# ADC.net
KiCad netlist of a schematic drawn in Altium Designer
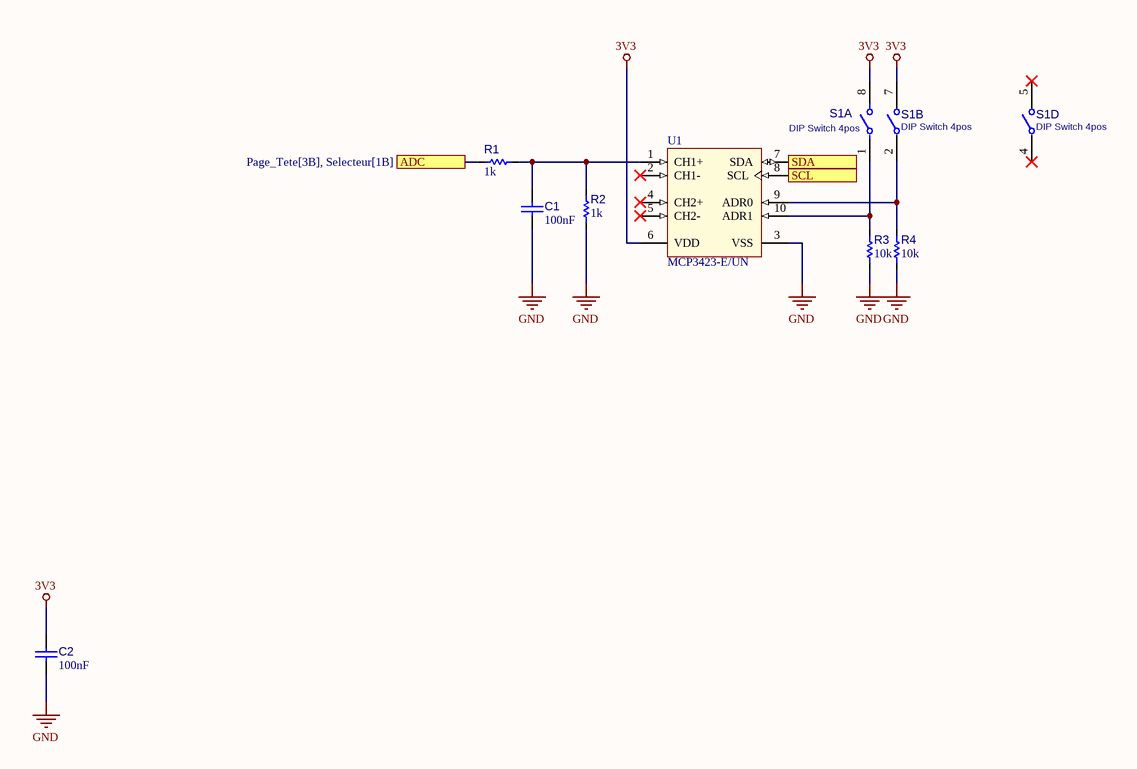
[diagram p0: ADC.SchDoc]

(export (version "E")
  (design (tool "Eeschema 10.0.6"))
  (components
    (comp (ref "C1")
      (value "100nF")
      (footprint "C_1608[0603]")
      (description "Capacitor type 1")
      (fields (field (name "TOLERANCE") "10%") (field (name "Comment") "CAP CER 100nF 50V 0603"))
      (libsource (lib "TEP-AltiumLib-Passives-RLC") (part "capacitor"))
    )
    (comp (ref "C2")
      (value "100nF")
      (footprint "C_1608[0603]")
      (description "Capacitor type 1")
      (fields (field (name "TOLERANCE") "10%") (field (name "Comment") "CAP CER 100nF 50V 0603"))
      (libsource (lib "TEP-AltiumLib-Passives-RLC") (part "capacitor"))
    )
    (comp (ref "R1")
      (value "1k")
      (footprint "R_1608[0603]")
      (description "Resistor type 1")
      (fields (field (name "TOLERANCE") "1%") (field (name "Comment") "Res 1k 1% 0603"))
      (libsource (lib "TEP-AltiumLib-Passives-RLC") (part "resistor"))
    )
    (comp (ref "R2")
      (value "1k")
      (footprint "R_1608[0603]")
      (description "Resistor type 1")
      (fields (field (name "TOLERANCE") "1%") (field (name "Comment") "Res 1k 1% 0603"))
      (libsource (lib "TEP-AltiumLib-Passives-RLC") (part "resistor"))
    )
    (comp (ref "R3")
      (value "10k")
      (footprint "R_1608[0603]")
      (description "Resistor type 1")
      (fields (field (name "TOLERANCE") "1%") (field (name "Comment") "Res 10k 1% 0603"))
      (libsource (lib "TEP-AltiumLib-Passives-RLC") (part "resistor"))
    )
    (comp (ref "R4")
      (value "10k")
      (footprint "R_1608[0603]")
      (description "Resistor type 1")
      (fields (field (name "TOLERANCE") "1%") (field (name "Comment") "Res 10k 1% 0603"))
      (libsource (lib "TEP-AltiumLib-Passives-RLC") (part "resistor"))
    )
    (comp (ref "S1")
      (value "DIP Switch 4pos")
      (footprint "S_DIP_SWITCH_50MIL_4POS")
      (description "SWITCH DIP SLIDE SPST 25MA 24V, pitch 1.27mm, height 1.55mm")
      (fields (field (name "Comment") "DSHP04TSGER"))
      (libsource (lib "TEP-AltiumLib") (part "SW_DIP_50MIL_4POS"))
    )
    (comp (ref "U1")
      (value "MCP3423-E/UN")
      (footprint "U_MSOP50P300X500-10(RM-10)_WO-TP")
      (description "CAN Controller Stand-Alone With SPI, 18-Pin PDIP")
      (libsource (lib "TEP-AltiumLib-ICs") (part "U_MCP3423-E/UN"))
    )
  )
  (nets
    (net (code "1") (name "/ADC") (class "Default")
      (node (ref "R1") (pin "1") (pinfunction "1_1") (pintype "passive"))
    )
    (net (code "2") (name "/SCL") (class "Default")
      (node (ref "U1") (pin "8") (pinfunction "SCL_8") (pintype "input"))
    )
    (net (code "3") (name "/SDA") (class "Default")
      (node (ref "U1") (pin "7") (pinfunction "SDA_7") (pintype "bidirectional"))
    )
    (net (code "4") (name "3V3") (class "Default")
      (node (ref "C2") (pin "2") (pinfunction "2_2") (pintype "passive"))
      (node (ref "S1") (pin "7") (pinfunction "7_7") (pintype "passive"))
      (node (ref "S1") (pin "8") (pinfunction "8_8") (pintype "passive"))
      (node (ref "U1") (pin "6") (pinfunction "VDD_6") (pintype "power_in"))
    )
    (net (code "5") (name "GND") (class "Default")
      (node (ref "C1") (pin "1") (pinfunction "1_1") (pintype "passive"))
      (node (ref "C2") (pin "1") (pinfunction "1_1") (pintype "passive"))
      (node (ref "R2") (pin "1") (pinfunction "1_1") (pintype "passive"))
      (node (ref "R3") (pin "1") (pinfunction "1_1") (pintype "passive"))
      (node (ref "R4") (pin "1") (pinfunction "1_1") (pintype "passive"))
      (node (ref "U1") (pin "3") (pinfunction "VSS_3") (pintype "power_in"))
    )
    (net (code "6") (name "Net-(U1-ADR0)") (class "Default")
      (node (ref "R4") (pin "2") (pinfunction "2_2") (pintype "passive"))
      (node (ref "S1") (pin "2") (pinfunction "2_2") (pintype "passive"))
      (node (ref "U1") (pin "9") (pinfunction "ADR0_9") (pintype "input"))
    )
    (net (code "7") (name "Net-(U1-ADR1)") (class "Default")
      (node (ref "R3") (pin "2") (pinfunction "2_2") (pintype "passive"))
      (node (ref "S1") (pin "1") (pinfunction "1_1") (pintype "passive"))
      (node (ref "U1") (pin "10") (pinfunction "ADR1_10") (pintype "input"))
    )
    (net (code "8") (name "Net-(U1-CH1+)") (class "Default")
      (node (ref "C1") (pin "2") (pinfunction "2_2") (pintype "passive"))
      (node (ref "R1") (pin "2") (pinfunction "2_2") (pintype "passive"))
      (node (ref "R2") (pin "2") (pinfunction "2_2") (pintype "passive"))
      (node (ref "U1") (pin "1") (pinfunction "CH1+_1") (pintype "input"))
    )
    (net (code "9") (name "unconnected-(S1-Pad4)") (class "Default")
      (node (ref "S1") (pin "4") (pinfunction "4_4") (pintype "passive+no_connect"))
    )
    (net (code "10") (name "unconnected-(S1-Pad5)") (class "Default")
      (node (ref "S1") (pin "5") (pinfunction "5_5") (pintype "passive+no_connect"))
    )
    (net (code "11") (name "unconnected-(U1-CH1--Pad2)") (class "Default")
      (node (ref "U1") (pin "2") (pinfunction "CH1-_2") (pintype "input+no_connect"))
    )
    (net (code "12") (name "unconnected-(U1-CH2+-Pad4)") (class "Default")
      (node (ref "U1") (pin "4") (pinfunction "CH2+_4") (pintype "input+no_connect"))
    )
    (net (code "13") (name "unconnected-(U1-CH2--Pad5)") (class "Default")
      (node (ref "U1") (pin "5") (pinfunction "CH2-_5") (pintype "input+no_connect"))
    )
  )
)
